# OPEN_SPECTRO_PI_HAT.net
KiCad netlist of a schematic drawn in EAGLE
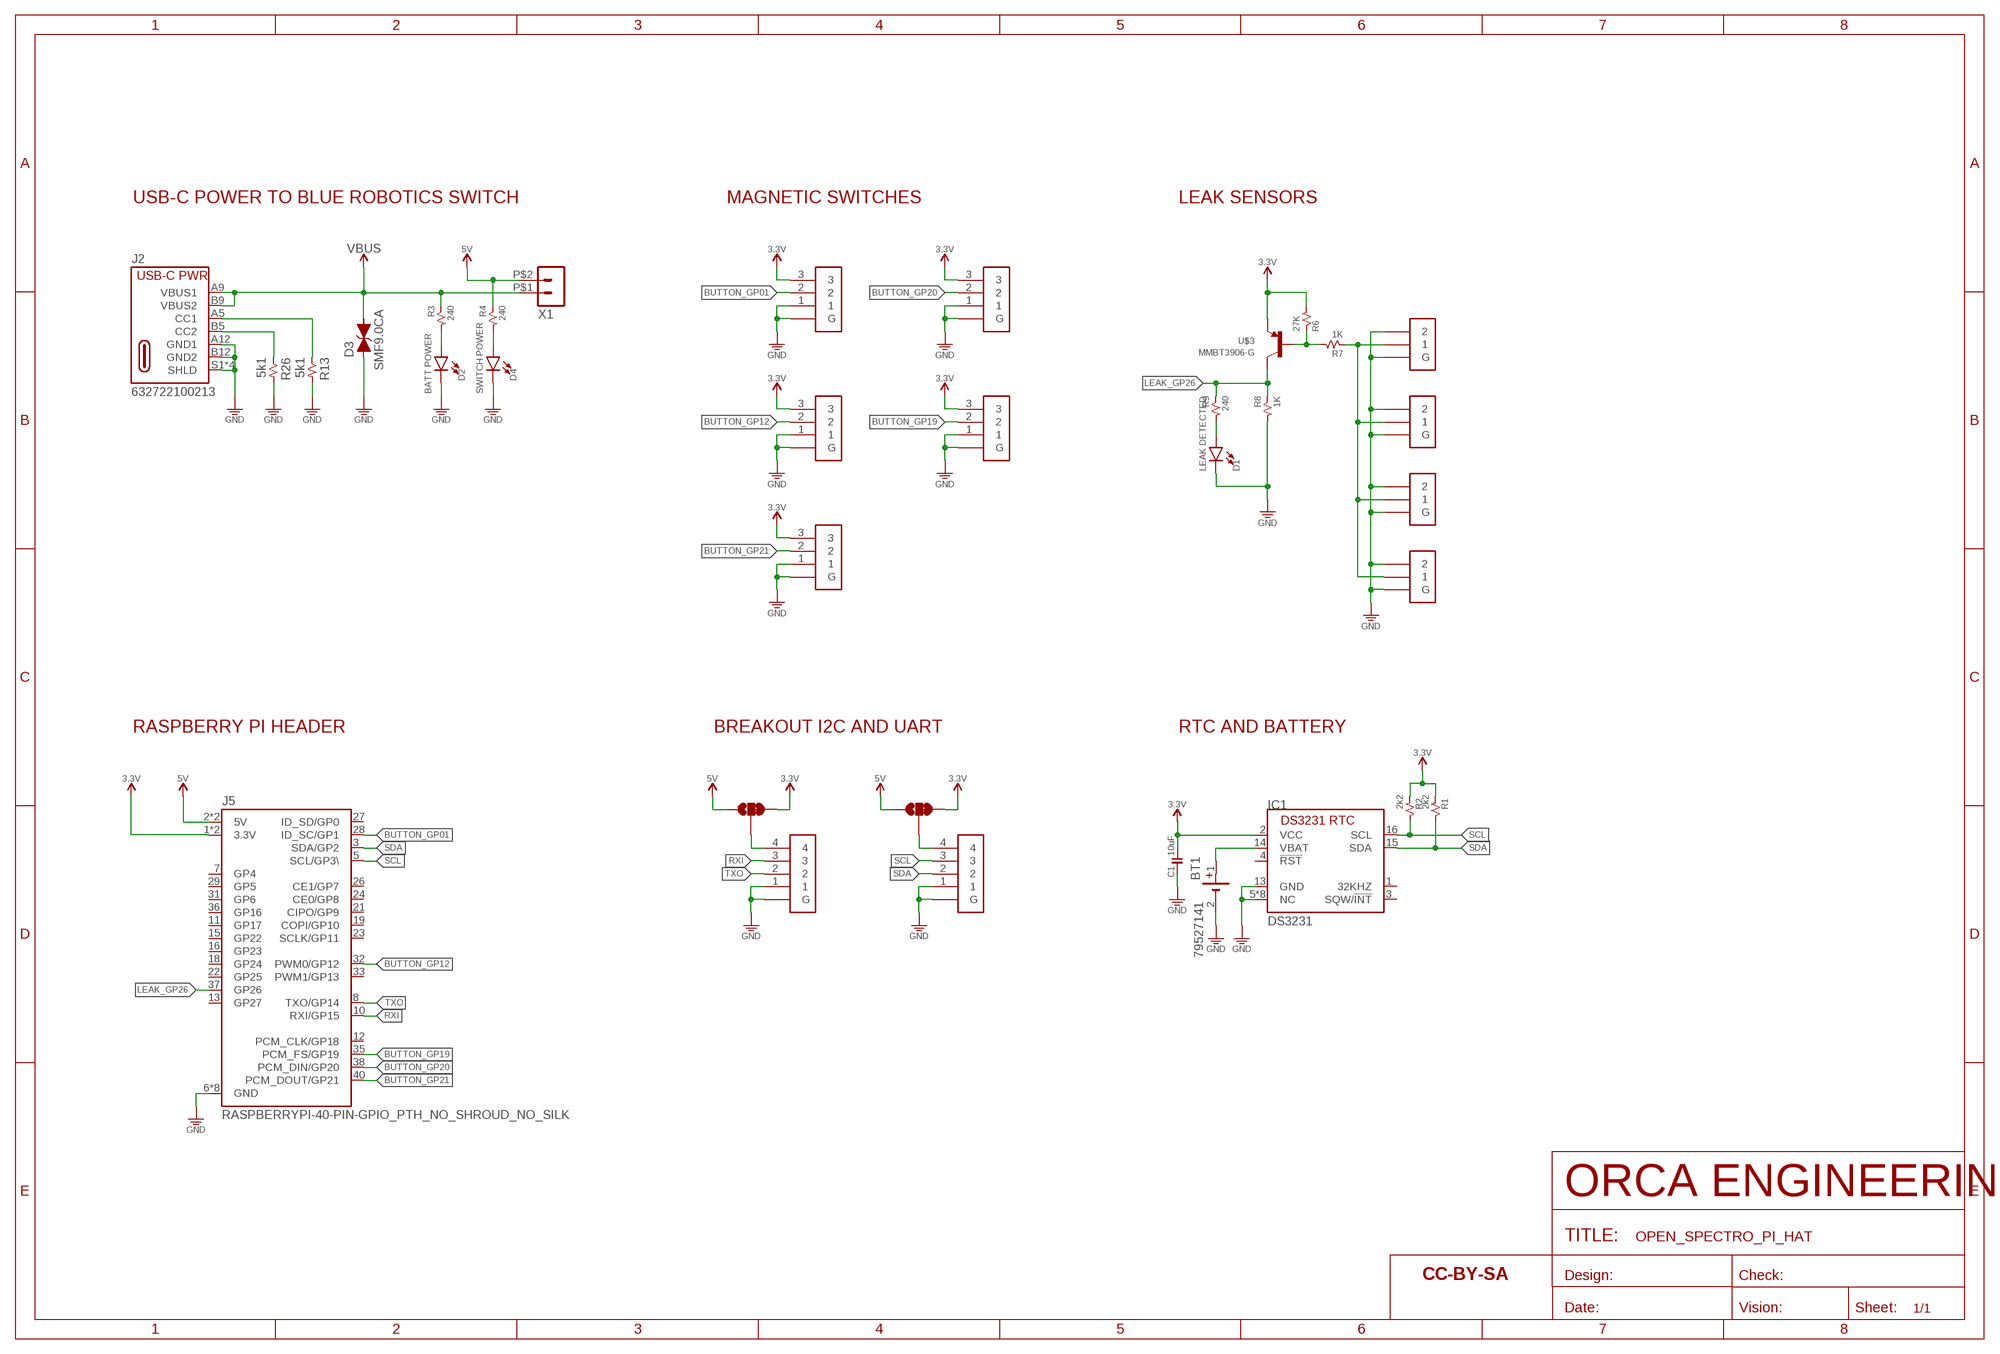
[diagram p0: schematic, sheet 1]

(export (version "E")
  (design (tool "Eeschema 10.0.6"))
  (components
    (comp (ref "BT1")
      (value "79527141")
      (footprint "eagle-import:79527141")
      (fields
        (field (name "DIGIKEY_PART_NO") "732-12325-2-ND")
        (field (name "MANUFACTURER") "Wurth Electronics Inc.")
        (field (name "CREATED_BY") "PCBLayout.com")
      )
      (libsource (lib "eagle-import") (part "79527141"))
    )
    (comp (ref "C1")
      (value "10uF")
      (footprint "eagle-import:0805")
      (libsource (lib "eagle-import") (part "0805"))
    )
    (comp (ref "D1")
      (value "LEAK DETECTED")
      (footprint "eagle-import:0805_LED")
      (libsource (lib "eagle-import") (part "LED0805"))
    )
    (comp (ref "D2")
      (value "BATT POWER")
      (footprint "eagle-import:0805_LED")
      (libsource (lib "eagle-import") (part "LED0805"))
    )
    (comp (ref "D3")
      (value "SMF9.0CA")
      (footprint "eagle-import:SOD-123F-TVS")
      (libsource (lib "eagle-import") (part "DIODE-TVS-BIDIRECTIONALSMF18CA"))
    )
    (comp (ref "D4")
      (value "SWITCH POWER")
      (footprint "eagle-import:0805_LED")
      (libsource (lib "eagle-import") (part "LED0805"))
    )
    (comp (ref "IC1")
      (value "DS3231/SO")
      (footprint "eagle-import:SO16W")
      (libsource (lib "eagle-import") (part "DS3231/SO"))
    )
    (comp (ref "J2")
      (value "632722100213")
      (footprint "eagle-import:632722100213")
      (libsource (lib "eagle-import") (part "USB-C_PWR_6_PIN"))
    )
    (comp (ref "J5")
      (value "RASPBERRYPI-40-PIN-GPIO_PTH_NO_SHROUD_NO_SILK")
      (footprint "eagle-import:2X20_NOSILK")
      (libsource (lib "eagle-import") (part "RASPBERRYPI-40-PIN-GPIO_PTH_NO_SHROUD_NO_SILK"))
    )
    (comp (ref "JP1")
      (value "JUMPER-SMT_3_1-NC_TRACE_SILK")
      (footprint "eagle-import:SMT-JUMPER_3_1-NC_TRACE_SILK")
      (libsource (lib "eagle-import") (part "JUMPER-SMT_3_1-NC_TRACE_SILK"))
    )
    (comp (ref "JP2")
      (value "JUMPER-SMT_3_1-NC_TRACE_SILK")
      (footprint "eagle-import:SMT-JUMPER_3_1-NC_TRACE_SILK")
      (libsource (lib "eagle-import") (part "JUMPER-SMT_3_1-NC_TRACE_SILK"))
    )
    (comp (ref "R1")
      (value "2k2")
      (footprint "eagle-import:0805")
      (libsource (lib "eagle-import") (part "_L_Resistors_vf.673Dwt_LQuWdsXra6AjxcA_0805"))
    )
    (comp (ref "R2")
      (value "2k2")
      (footprint "eagle-import:0805")
      (libsource (lib "eagle-import") (part "_L_Resistors_vf.673Dwt_LQuWdsXra6AjxcA_0805"))
    )
    (comp (ref "R3")
      (value "240")
      (footprint "eagle-import:0805")
      (libsource (lib "eagle-import") (part "_L_Resistors_vf.673Dwt_LQuWdsXra6AjxcA_0805"))
    )
    (comp (ref "R4")
      (value "240")
      (footprint "eagle-import:0805")
      (libsource (lib "eagle-import") (part "_L_Resistors_vf.673Dwt_LQuWdsXra6AjxcA_0805"))
    )
    (comp (ref "R6")
      (value "27K")
      (footprint "eagle-import:0805")
      (libsource (lib "eagle-import") (part "_L_Resistors_vf.673Dwt_LQuWdsXra6AjxcA_0805"))
    )
    (comp (ref "R7")
      (value "1K")
      (footprint "eagle-import:0805")
      (libsource (lib "eagle-import") (part "_L_Resistors_vf.673Dwt_LQuWdsXra6AjxcA_0805"))
    )
    (comp (ref "R8")
      (value "1K")
      (footprint "eagle-import:0805")
      (libsource (lib "eagle-import") (part "_L_Resistors_vf.673Dwt_LQuWdsXra6AjxcA_0805"))
    )
    (comp (ref "R9")
      (value "240")
      (footprint "eagle-import:0805")
      (libsource (lib "eagle-import") (part "_L_Resistors_vf.673Dwt_LQuWdsXra6AjxcA_0805"))
    )
    (comp (ref "R13")
      (value "5k1")
      (footprint "eagle-import:0805")
      (libsource (lib "eagle-import") (part "_L_Resistors_vf.673Dwt_LQuWdsXra6AjxcA_0805"))
    )
    (comp (ref "R26")
      (value "5k1")
      (footprint "eagle-import:0805")
      (libsource (lib "eagle-import") (part "_L_Resistors_vf.673Dwt_LQuWdsXra6AjxcA_0805"))
    )
    (comp (ref "U$1")
      (value "JST-GH-2SIDE")
      (footprint "eagle-import:JST-GH-SIDE-2")
      (libsource (lib "eagle-import") (part "JST-GH-2SIDE"))
    )
    (comp (ref "U$2")
      (value "JST-GH-2SIDE")
      (footprint "eagle-import:JST-GH-SIDE-2")
      (libsource (lib "eagle-import") (part "JST-GH-2SIDE"))
    )
    (comp (ref "U$3")
      (value "MMBT3906-G")
      (footprint "eagle-import:SOT23-3_GENERIC")
      (libsource (lib "eagle-import") (part "TRANS_PNPMMBT3906-G"))
    )
    (comp (ref "U$4")
      (value "JST-GH-3SIDE")
      (footprint "eagle-import:JST-GH-SIDE-3")
      (libsource (lib "eagle-import") (part "JST-GH-3SIDE"))
    )
    (comp (ref "U$5")
      (value "JST-GH-2SIDE")
      (footprint "eagle-import:JST-GH-SIDE-2")
      (libsource (lib "eagle-import") (part "JST-GH-2SIDE"))
    )
    (comp (ref "U$6")
      (value "JST-GH-2SIDE")
      (footprint "eagle-import:JST-GH-SIDE-2")
      (libsource (lib "eagle-import") (part "JST-GH-2SIDE"))
    )
    (comp (ref "U$7")
      (value "JST-GH-4SIDE")
      (footprint "eagle-import:JST-GH-SIDE-4")
      (libsource (lib "eagle-import") (part "JST-GH-4SIDE"))
    )
    (comp (ref "U$8")
      (value "JST-GH-4SIDE")
      (footprint "eagle-import:JST-GH-SIDE-4")
      (libsource (lib "eagle-import") (part "JST-GH-4SIDE"))
    )
    (comp (ref "U$11")
      (value "JST-GH-3SIDE")
      (footprint "eagle-import:JST-GH-SIDE-3")
      (libsource (lib "eagle-import") (part "JST-GH-3SIDE"))
    )
    (comp (ref "U$12")
      (value "JST-GH-3SIDE")
      (footprint "eagle-import:JST-GH-SIDE-3")
      (libsource (lib "eagle-import") (part "JST-GH-3SIDE"))
    )
    (comp (ref "U$14")
      (value "JST-GH-3SIDE")
      (footprint "eagle-import:JST-GH-SIDE-3")
      (libsource (lib "eagle-import") (part "JST-GH-3SIDE"))
    )
    (comp (ref "U$15")
      (value "JST-GH-3SIDE")
      (footprint "eagle-import:JST-GH-SIDE-3")
      (libsource (lib "eagle-import") (part "JST-GH-3SIDE"))
    )
    (comp (ref "X1")
      (value "MICRO-FIT_02P43650-0200")
      (footprint "eagle-import:43650-0200")
      (libsource (lib "eagle-import") (part "MICRO-FIT_02P43650-0200"))
    )
  )
  (nets
    (net (code "1") (name "3.3V") (class "Default")
      (node (ref "C1") (pin "1") (pinfunction "1_1") (pintype "passive"))
      (node (ref "IC1") (pin "2") (pinfunction "VCC_2") (pintype "power_in"))
      (node (ref "J5") (pin "1") (pinfunction "3.3V_1") (pintype "power_in"))
      (node (ref "J5") (pin "17") (pinfunction "3.3V_17") (pintype "power_in"))
      (node (ref "JP1") (pin "3") (pinfunction "3_3") (pintype "passive"))
      (node (ref "JP2") (pin "3") (pinfunction "3_3") (pintype "passive"))
      (node (ref "R1") (pin "2") (pinfunction "2_2") (pintype "passive"))
      (node (ref "R2") (pin "2") (pinfunction "2_2") (pintype "passive"))
      (node (ref "R6") (pin "2") (pinfunction "2_2") (pintype "passive"))
      (node (ref "U$11") (pin "3") (pinfunction "3_3") (pintype "bidirectional"))
      (node (ref "U$12") (pin "3") (pinfunction "3_3") (pintype "bidirectional"))
      (node (ref "U$14") (pin "3") (pinfunction "3_3") (pintype "bidirectional"))
      (node (ref "U$15") (pin "3") (pinfunction "3_3") (pintype "bidirectional"))
      (node (ref "U$3") (pin "3") (pinfunction "C_3") (pintype "passive"))
      (node (ref "U$4") (pin "3") (pinfunction "3_3") (pintype "bidirectional"))
    )
    (net (code "2") (name "5V") (class "Default")
      (node (ref "J5") (pin "2") (pinfunction "5V_2") (pintype "power_in"))
      (node (ref "J5") (pin "4") (pinfunction "5V_4") (pintype "power_in"))
      (node (ref "JP1") (pin "1") (pinfunction "1_1") (pintype "passive"))
      (node (ref "JP2") (pin "1") (pinfunction "1_1") (pintype "passive"))
      (node (ref "R4") (pin "1") (pinfunction "1_1") (pintype "passive"))
      (node (ref "X1") (pin "P$2") (pinfunction "2_P$2") (pintype "passive"))
    )
    (net (code "3") (name "BUTTON_GP01") (class "Default")
      (node (ref "J5") (pin "28") (pinfunction "ID_SC/GP1_28") (pintype "bidirectional"))
      (node (ref "U$4") (pin "2") (pinfunction "2_2") (pintype "bidirectional"))
    )
    (net (code "4") (name "BUTTON_GP12") (class "Default")
      (node (ref "J5") (pin "32") (pinfunction "PWM0/GP12_32") (pintype "bidirectional"))
      (node (ref "U$11") (pin "2") (pinfunction "2_2") (pintype "bidirectional"))
    )
    (net (code "5") (name "BUTTON_GP19") (class "Default")
      (node (ref "J5") (pin "35") (pinfunction "PCM_FS/GP19_35") (pintype "bidirectional"))
      (node (ref "U$15") (pin "2") (pinfunction "2_2") (pintype "bidirectional"))
    )
    (net (code "6") (name "BUTTON_GP20") (class "Default")
      (node (ref "J5") (pin "38") (pinfunction "PCM_DIN/GP20_38") (pintype "bidirectional"))
      (node (ref "U$14") (pin "2") (pinfunction "2_2") (pintype "bidirectional"))
    )
    (net (code "7") (name "BUTTON_GP21") (class "Default")
      (node (ref "J5") (pin "40") (pinfunction "PCM_DOUT/GP21_40") (pintype "bidirectional"))
      (node (ref "U$12") (pin "2") (pinfunction "2_2") (pintype "bidirectional"))
    )
    (net (code "8") (name "GND") (class "Default")
      (node (ref "BT1") (pin "2") (pinfunction "-_2") (pintype "passive"))
      (node (ref "C1") (pin "2") (pinfunction "2_2") (pintype "passive"))
      (node (ref "D1") (pin "C") (pinfunction "C_C") (pintype "passive"))
      (node (ref "D2") (pin "C") (pinfunction "C_C") (pintype "passive"))
      (node (ref "D3") (pin "A") (pinfunction "C1_A") (pintype "passive"))
      (node (ref "D4") (pin "C") (pinfunction "C_C") (pintype "passive"))
      (node (ref "IC1") (pin "10") (pinfunction "NC_10") (pintype "power_in"))
      (node (ref "IC1") (pin "11") (pinfunction "NC_11") (pintype "power_in"))
      (node (ref "IC1") (pin "12") (pinfunction "NC_12") (pintype "power_in"))
      (node (ref "IC1") (pin "13") (pinfunction "GND_13") (pintype "power_in"))
      (node (ref "IC1") (pin "5") (pinfunction "NC_5") (pintype "power_in"))
      (node (ref "IC1") (pin "6") (pinfunction "NC_6") (pintype "power_in"))
      (node (ref "IC1") (pin "7") (pinfunction "NC_7") (pintype "power_in"))
      (node (ref "IC1") (pin "8") (pinfunction "NC_8") (pintype "power_in"))
      (node (ref "IC1") (pin "9") (pinfunction "NC_9") (pintype "power_in"))
      (node (ref "J2") (pin "A12") (pinfunction "GND1_A12") (pintype "passive"))
      (node (ref "J2") (pin "B12") (pinfunction "GND2_B12") (pintype "passive"))
      (node (ref "J2") (pin "S1") (pinfunction "SHLD_S1") (pintype "passive"))
      (node (ref "J2") (pin "S2") (pinfunction "SHLD_S2") (pintype "passive"))
      (node (ref "J2") (pin "S3") (pinfunction "SHLD_S3") (pintype "passive"))
      (node (ref "J2") (pin "S4") (pinfunction "SHLD_S4") (pintype "passive"))
      (node (ref "J5") (pin "14") (pinfunction "GND_14") (pintype "power_in"))
      (node (ref "J5") (pin "20") (pinfunction "GND_20") (pintype "power_in"))
      (node (ref "J5") (pin "25") (pinfunction "GND_25") (pintype "power_in"))
      (node (ref "J5") (pin "30") (pinfunction "GND_30") (pintype "power_in"))
      (node (ref "J5") (pin "34") (pinfunction "GND_34") (pintype "power_in"))
      (node (ref "J5") (pin "39") (pinfunction "GND_39") (pintype "power_in"))
      (node (ref "J5") (pin "6") (pinfunction "GND_6") (pintype "power_in"))
      (node (ref "J5") (pin "9") (pinfunction "GND_9") (pintype "power_in"))
      (node (ref "R13") (pin "2") (pinfunction "2_2") (pintype "passive"))
      (node (ref "R26") (pin "2") (pinfunction "2_2") (pintype "passive"))
      (node (ref "R8") (pin "2") (pinfunction "2_2") (pintype "passive"))
      (node (ref "U$1") (pin "2") (pinfunction "2_2") (pintype "bidirectional"))
      (node (ref "U$1") (pin "MECH1") (pinfunction "G_MECH1") (pintype "bidirectional"))
      (node (ref "U$1") (pin "MECH2") (pinfunction "G_MECH2") (pintype "bidirectional"))
      (node (ref "U$11") (pin "1") (pinfunction "1_1") (pintype "bidirectional"))
      (node (ref "U$11") (pin "MECH1") (pinfunction "G_MECH1") (pintype "bidirectional"))
      (node (ref "U$11") (pin "MECH2") (pinfunction "G_MECH2") (pintype "bidirectional"))
      (node (ref "U$12") (pin "1") (pinfunction "1_1") (pintype "bidirectional"))
      (node (ref "U$12") (pin "MECH1") (pinfunction "G_MECH1") (pintype "bidirectional"))
      (node (ref "U$12") (pin "MECH2") (pinfunction "G_MECH2") (pintype "bidirectional"))
      (node (ref "U$14") (pin "1") (pinfunction "1_1") (pintype "bidirectional"))
      (node (ref "U$14") (pin "MECH1") (pinfunction "G_MECH1") (pintype "bidirectional"))
      (node (ref "U$14") (pin "MECH2") (pinfunction "G_MECH2") (pintype "bidirectional"))
      (node (ref "U$15") (pin "1") (pinfunction "1_1") (pintype "bidirectional"))
      (node (ref "U$15") (pin "MECH1") (pinfunction "G_MECH1") (pintype "bidirectional"))
      (node (ref "U$15") (pin "MECH2") (pinfunction "G_MECH2") (pintype "bidirectional"))
      (node (ref "U$2") (pin "2") (pinfunction "2_2") (pintype "bidirectional"))
      (node (ref "U$2") (pin "MECH1") (pinfunction "G_MECH1") (pintype "bidirectional"))
      (node (ref "U$2") (pin "MECH2") (pinfunction "G_MECH2") (pintype "bidirectional"))
      (node (ref "U$4") (pin "1") (pinfunction "1_1") (pintype "bidirectional"))
      (node (ref "U$4") (pin "MECH1") (pinfunction "G_MECH1") (pintype "bidirectional"))
      (node (ref "U$4") (pin "MECH2") (pinfunction "G_MECH2") (pintype "bidirectional"))
      (node (ref "U$5") (pin "2") (pinfunction "2_2") (pintype "bidirectional"))
      (node (ref "U$5") (pin "MECH1") (pinfunction "G_MECH1") (pintype "bidirectional"))
      (node (ref "U$5") (pin "MECH2") (pinfunction "G_MECH2") (pintype "bidirectional"))
      (node (ref "U$6") (pin "2") (pinfunction "2_2") (pintype "bidirectional"))
      (node (ref "U$6") (pin "MECH1") (pinfunction "G_MECH1") (pintype "bidirectional"))
      (node (ref "U$6") (pin "MECH2") (pinfunction "G_MECH2") (pintype "bidirectional"))
      (node (ref "U$7") (pin "1") (pinfunction "1_1") (pintype "bidirectional"))
      (node (ref "U$7") (pin "MECH1") (pinfunction "G_MECH1") (pintype "bidirectional"))
      (node (ref "U$7") (pin "MECH2") (pinfunction "G_MECH2") (pintype "bidirectional"))
      (node (ref "U$8") (pin "1") (pinfunction "1_1") (pintype "bidirectional"))
      (node (ref "U$8") (pin "MECH1") (pinfunction "G_MECH1") (pintype "bidirectional"))
      (node (ref "U$8") (pin "MECH2") (pinfunction "G_MECH2") (pintype "bidirectional"))
    )
    (net (code "9") (name "LEAK_GP26") (class "Default")
      (node (ref "J5") (pin "37") (pinfunction "GP26_37") (pintype "bidirectional"))
      (node (ref "R8") (pin "1") (pinfunction "1_1") (pintype "passive"))
      (node (ref "R9") (pin "1") (pinfunction "1_1") (pintype "passive"))
      (node (ref "U$3") (pin "2") (pinfunction "E_2") (pintype "passive"))
    )
    (net (code "10") (name "Net-(BT1-+)") (class "Default")
      (node (ref "BT1") (pin "1") (pinfunction "+_1") (pintype "passive"))
      (node (ref "IC1") (pin "14") (pinfunction "VBAT_14") (pintype "power_in"))
    )
    (net (code "11") (name "Net-(D1-PadA)") (class "Default")
      (node (ref "D1") (pin "A") (pinfunction "A_A") (pintype "passive"))
      (node (ref "R9") (pin "2") (pinfunction "2_2") (pintype "passive"))
    )
    (net (code "12") (name "Net-(D2-PadA)") (class "Default")
      (node (ref "D2") (pin "A") (pinfunction "A_A") (pintype "passive"))
      (node (ref "R3") (pin "2") (pinfunction "2_2") (pintype "passive"))
    )
    (net (code "13") (name "Net-(D4-PadA)") (class "Default")
      (node (ref "D4") (pin "A") (pinfunction "A_A") (pintype "passive"))
      (node (ref "R4") (pin "2") (pinfunction "2_2") (pintype "passive"))
    )
    (net (code "14") (name "Net-(J2-CC1)") (class "Default")
      (node (ref "J2") (pin "A5") (pinfunction "CC1_A5") (pintype "passive"))
      (node (ref "R13") (pin "1") (pinfunction "1_1") (pintype "passive"))
    )
    (net (code "15") (name "Net-(J2-CC2)") (class "Default")
      (node (ref "J2") (pin "B5") (pinfunction "CC2_B5") (pintype "passive"))
      (node (ref "R26") (pin "1") (pinfunction "1_1") (pintype "passive"))
    )
    (net (code "16") (name "Net-(JP1-Pad2)") (class "Default")
      (node (ref "JP1") (pin "2") (pinfunction "2_2") (pintype "passive"))
      (node (ref "U$7") (pin "4") (pinfunction "4_4") (pintype "bidirectional"))
    )
    (net (code "17") (name "Net-(JP2-Pad2)") (class "Default")
      (node (ref "JP2") (pin "2") (pinfunction "2_2") (pintype "passive"))
      (node (ref "U$8") (pin "4") (pinfunction "4_4") (pintype "bidirectional"))
    )
    (net (code "18") (name "Net-(R7-Pad2)") (class "Default")
      (node (ref "R7") (pin "2") (pinfunction "2_2") (pintype "passive"))
      (node (ref "U$1") (pin "1") (pinfunction "1_1") (pintype "bidirectional"))
      (node (ref "U$2") (pin "1") (pinfunction "1_1") (pintype "bidirectional"))
      (node (ref "U$5") (pin "1") (pinfunction "1_1") (pintype "bidirectional"))
      (node (ref "U$6") (pin "1") (pinfunction "1_1") (pintype "bidirectional"))
    )
    (net (code "19") (name "Net-(U$3-B)") (class "Default")
      (node (ref "R6") (pin "1") (pinfunction "1_1") (pintype "passive"))
      (node (ref "R7") (pin "1") (pinfunction "1_1") (pintype "passive"))
      (node (ref "U$3") (pin "1") (pinfunction "B_1") (pintype "passive"))
    )
    (net (code "20") (name "RXI") (class "Default")
      (node (ref "J5") (pin "10") (pinfunction "RXI/GP15_10") (pintype "input"))
      (node (ref "U$8") (pin "3") (pinfunction "3_3") (pintype "bidirectional"))
    )
    (net (code "21") (name "SCL") (class "Default")
      (node (ref "IC1") (pin "16") (pinfunction "SCL_16") (pintype "bidirectional"))
      (node (ref "J5") (pin "5") (pinfunction "SCL/GP3\\_5") (pintype "bidirectional"))
      (node (ref "R2") (pin "1") (pinfunction "1_1") (pintype "passive"))
      (node (ref "U$7") (pin "3") (pinfunction "3_3") (pintype "bidirectional"))
    )
    (net (code "22") (name "SDA") (class "Default")
      (node (ref "IC1") (pin "15") (pinfunction "SDA_15") (pintype "bidirectional"))
      (node (ref "J5") (pin "3") (pinfunction "SDA/GP2_3") (pintype "bidirectional"))
      (node (ref "R1") (pin "1") (pinfunction "1_1") (pintype "passive"))
      (node (ref "U$7") (pin "2") (pinfunction "2_2") (pintype "bidirectional"))
    )
    (net (code "23") (name "TXO") (class "Default")
      (node (ref "J5") (pin "8") (pinfunction "TXO/GP14_8") (pintype "output"))
      (node (ref "U$8") (pin "2") (pinfunction "2_2") (pintype "bidirectional"))
    )
    (net (code "24") (name "VBUS") (class "Default")
      (node (ref "D3") (pin "C") (pinfunction "C2_C") (pintype "passive"))
      (node (ref "J2") (pin "A9") (pinfunction "VBUS1_A9") (pintype "passive"))
      (node (ref "J2") (pin "B9") (pinfunction "VBUS2_B9") (pintype "passive"))
      (node (ref "R3") (pin "1") (pinfunction "1_1") (pintype "passive"))
      (node (ref "X1") (pin "P$1") (pinfunction "1_P$1") (pintype "passive"))
    )
    (net (code "25") (name "unconnected-(IC1-32KHZ-Pad1)") (class "Default")
      (node (ref "IC1") (pin "1") (pinfunction "32KHZ_1") (pintype "output"))
    )
    (net (code "26") (name "unconnected-(IC1-SQW{slash}~{INT}-Pad3)") (class "Default")
      (node (ref "IC1") (pin "3") (pinfunction "SQW/~{INT}_3") (pintype "output"))
    )
    (net (code "27") (name "unconnected-(IC1-~{RST}-Pad4)") (class "Default")
      (node (ref "IC1") (pin "4") (pinfunction "~{RST}_4") (pintype "bidirectional"))
    )
    (net (code "28") (name "unconnected-(J5-CE0{slash}GP8-Pad24)") (class "Default")
      (node (ref "J5") (pin "24") (pinfunction "CE0/GP8_24") (pintype "output"))
    )
    (net (code "29") (name "unconnected-(J5-CE1{slash}GP7-Pad26)") (class "Default")
      (node (ref "J5") (pin "26") (pinfunction "CE1/GP7_26") (pintype "output"))
    )
    (net (code "30") (name "unconnected-(J5-CIPO{slash}GP9-Pad21)") (class "Default")
      (node (ref "J5") (pin "21") (pinfunction "CIPO/GP9_21") (pintype "input"))
    )
    (net (code "31") (name "unconnected-(J5-COPI{slash}GP10-Pad19)") (class "Default")
      (node (ref "J5") (pin "19") (pinfunction "COPI/GP10_19") (pintype "output"))
    )
    (net (code "32") (name "unconnected-(J5-GP4-Pad7)") (class "Default")
      (node (ref "J5") (pin "7") (pinfunction "GP4_7") (pintype "bidirectional"))
    )
    (net (code "33") (name "unconnected-(J5-GP5-Pad29)") (class "Default")
      (node (ref "J5") (pin "29") (pinfunction "GP5_29") (pintype "bidirectional"))
    )
    (net (code "34") (name "unconnected-(J5-GP6-Pad31)") (class "Default")
      (node (ref "J5") (pin "31") (pinfunction "GP6_31") (pintype "bidirectional"))
    )
    (net (code "35") (name "unconnected-(J5-GP16-Pad36)") (class "Default")
      (node (ref "J5") (pin "36") (pinfunction "GP16_36") (pintype "bidirectional"))
    )
    (net (code "36") (name "unconnected-(J5-GP17-Pad11)") (class "Default")
      (node (ref "J5") (pin "11") (pinfunction "GP17_11") (pintype "bidirectional"))
    )
    (net (code "37") (name "unconnected-(J5-GP22-Pad15)") (class "Default")
      (node (ref "J5") (pin "15") (pinfunction "GP22_15") (pintype "bidirectional"))
    )
    (net (code "38") (name "unconnected-(J5-GP23-Pad16)") (class "Default")
      (node (ref "J5") (pin "16") (pinfunction "GP23_16") (pintype "bidirectional"))
    )
    (net (code "39") (name "unconnected-(J5-GP24-Pad18)") (class "Default")
      (node (ref "J5") (pin "18") (pinfunction "GP24_18") (pintype "bidirectional"))
    )
    (net (code "40") (name "unconnected-(J5-GP25-Pad22)") (class "Default")
      (node (ref "J5") (pin "22") (pinfunction "GP25_22") (pintype "bidirectional"))
    )
    (net (code "41") (name "unconnected-(J5-GP27-Pad13)") (class "Default")
      (node (ref "J5") (pin "13") (pinfunction "GP27_13") (pintype "bidirectional"))
    )
    (net (code "42") (name "unconnected-(J5-ID_SD{slash}GP0-Pad27)") (class "Default")
      (node (ref "J5") (pin "27") (pinfunction "ID_SD/GP0_27") (pintype "bidirectional"))
    )
    (net (code "43") (name "unconnected-(J5-PCM_CLK{slash}GP18-Pad12)") (class "Default")
      (node (ref "J5") (pin "12") (pinfunction "PCM_CLK/GP18_12") (pintype "bidirectional"))
    )
    (net (code "44") (name "unconnected-(J5-PWM1{slash}GP13-Pad33)") (class "Default")
      (node (ref "J5") (pin "33") (pinfunction "PWM1/GP13_33") (pintype "bidirectional"))
    )
    (net (code "45") (name "unconnected-(J5-SCLK{slash}GP11-Pad23)") (class "Default")
      (node (ref "J5") (pin "23") (pinfunction "SCLK/GP11_23") (pintype "output"))
    )
  )
)
